# Buck.net
KiCad netlist of a schematic drawn in EAGLE
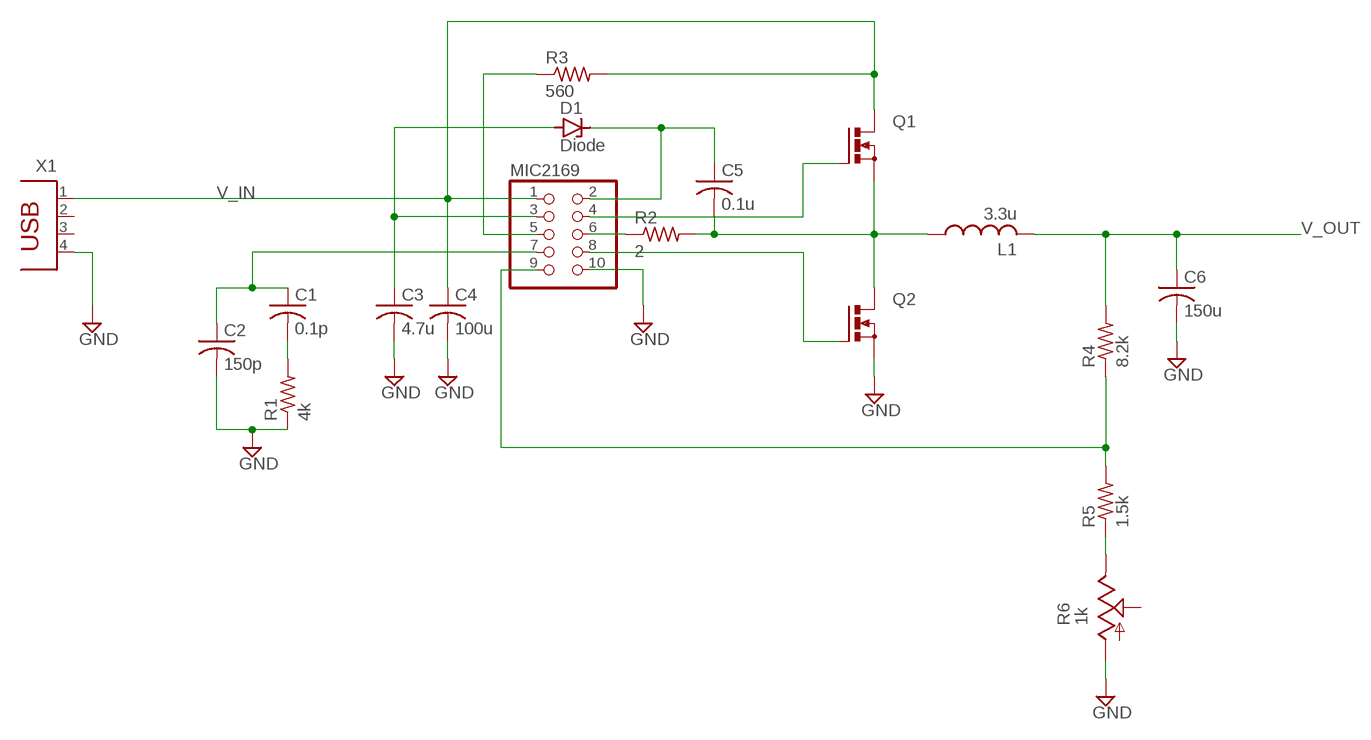
[diagram p0: schematic, sheet 1]

(export (version "E")
  (design (tool "Eeschema 10.0.6"))
  (components
    (comp (ref "C1")
      (value "0.1p")
      (footprint "eagle-import:C0805")
      (libsource (lib "eagle-import") (part "C-USC0805"))
    )
    (comp (ref "C2")
      (value "150p")
      (footprint "eagle-import:C0805")
      (libsource (lib "eagle-import") (part "C-USC0805"))
    )
    (comp (ref "C3")
      (value "4.7u")
      (footprint "eagle-import:C0805")
      (libsource (lib "eagle-import") (part "C-USC0805"))
    )
    (comp (ref "C4")
      (value "100u")
      (footprint "eagle-import:C0805")
      (libsource (lib "eagle-import") (part "C-USC0805"))
    )
    (comp (ref "C5")
      (value "0.1u")
      (footprint "eagle-import:C0805")
      (libsource (lib "eagle-import") (part "C-USC0805"))
    )
    (comp (ref "C6")
      (value "150u")
      (footprint "eagle-import:C0805")
      (libsource (lib "eagle-import") (part "C-USC0805"))
    )
    (comp (ref "D1")
      (value "Diode")
      (footprint "eagle-import:DO35Z10")
      (libsource (lib "eagle-import") (part "1N821"))
    )
    (comp (ref "L1")
      (value "3.3u")
      (footprint "eagle-import:L2825P")
      (libsource (lib "eagle-import") (part "L-USL2825P"))
    )
    (comp (ref "MIC2169")
      (value "PINHD-2X5")
      (footprint "eagle-import:2X05")
      (libsource (lib "eagle-import") (part "PINHD-2X5"))
    )
    (comp (ref "R1")
      (value "4k")
      (footprint "eagle-import:R0805")
      (libsource (lib "eagle-import") (part "R-US_R0805"))
    )
    (comp (ref "R2")
      (value "2")
      (footprint "eagle-import:R0805")
      (libsource (lib "eagle-import") (part "R-US_R0805"))
    )
    (comp (ref "R3")
      (value "560")
      (footprint "eagle-import:R0805")
      (libsource (lib "eagle-import") (part "R-US_R0805"))
    )
    (comp (ref "R4")
      (value "8.2k")
      (footprint "eagle-import:R0805")
      (libsource (lib "eagle-import") (part "R-US_R0805"))
    )
    (comp (ref "R5")
      (value "1.5k")
      (footprint "eagle-import:R0805")
      (libsource (lib "eagle-import") (part "R-US_R0805"))
    )
    (comp (ref "R6")
      (value "1k")
      (footprint "eagle-import:3223G")
      (libsource (lib "eagle-import") (part "TRIM_US-3223G"))
    )
    (comp (ref "X1")
      (value "PN61729")
      (footprint "eagle-import:PN61729")
      (libsource (lib "eagle-import") (part "PN61729"))
    )
  )
  (nets
    (net (code "1") (name "/V_IN") (class "Default")
      (node (ref "C4") (pin "1") (pinfunction "1_1") (pintype "passive"))
      (node (ref "MIC2169") (pin "1") (pinfunction "1_1") (pintype "passive"))
      (node (ref "R3") (pin "2") (pinfunction "2_2") (pintype "passive"))
      (node (ref "X1") (pin "1") (pinfunction "1_1") (pintype "passive"))
    )
    (net (code "2") (name "/V_OUT") (class "Default")
      (node (ref "C6") (pin "1") (pinfunction "1_1") (pintype "passive"))
      (node (ref "L1") (pin "2") (pinfunction "2_2") (pintype "passive"))
      (node (ref "R4") (pin "2") (pinfunction "2_2") (pintype "passive"))
    )
    (net (code "3") (name "GND") (class "Default")
      (node (ref "C2") (pin "2") (pinfunction "2_2") (pintype "passive"))
      (node (ref "C3") (pin "2") (pinfunction "2_2") (pintype "passive"))
      (node (ref "C4") (pin "2") (pinfunction "2_2") (pintype "passive"))
      (node (ref "C6") (pin "2") (pinfunction "2_2") (pintype "passive"))
      (node (ref "MIC2169") (pin "10") (pinfunction "10_10") (pintype "passive"))
      (node (ref "R1") (pin "1") (pinfunction "1_1") (pintype "passive"))
      (node (ref "R6") (pin "1") (pinfunction "A_1") (pintype "passive"))
      (node (ref "X1") (pin "4") (pinfunction "4_4") (pintype "passive"))
    )
    (net (code "4") (name "Net-(C1-Pad1)") (class "Default")
      (node (ref "C1") (pin "1") (pinfunction "1_1") (pintype "passive"))
      (node (ref "C2") (pin "1") (pinfunction "1_1") (pintype "passive"))
      (node (ref "MIC2169") (pin "7") (pinfunction "7_7") (pintype "passive"))
    )
    (net (code "5") (name "Net-(C1-Pad2)") (class "Default")
      (node (ref "C1") (pin "2") (pinfunction "2_2") (pintype "passive"))
      (node (ref "R1") (pin "2") (pinfunction "2_2") (pintype "passive"))
    )
    (net (code "6") (name "Net-(C3-Pad1)") (class "Default")
      (node (ref "C3") (pin "1") (pinfunction "1_1") (pintype "passive"))
      (node (ref "D1") (pin "A") (pinfunction "A_A") (pintype "passive"))
      (node (ref "MIC2169") (pin "3") (pinfunction "3_3") (pintype "passive"))
    )
    (net (code "7") (name "Net-(C5-Pad1)") (class "Default")
      (node (ref "C5") (pin "1") (pinfunction "1_1") (pintype "passive"))
      (node (ref "D1") (pin "C") (pinfunction "C_C") (pintype "passive"))
      (node (ref "MIC2169") (pin "2") (pinfunction "2_2") (pintype "passive"))
    )
    (net (code "8") (name "Net-(C5-Pad2)") (class "Default")
      (node (ref "C5") (pin "2") (pinfunction "2_2") (pintype "passive"))
      (node (ref "L1") (pin "1") (pinfunction "1_1") (pintype "passive"))
      (node (ref "R2") (pin "2") (pinfunction "2_2") (pintype "passive"))
    )
    (net (code "9") (name "Net-(MIC2169-Pad5)") (class "Default")
      (node (ref "MIC2169") (pin "5") (pinfunction "5_5") (pintype "passive"))
      (node (ref "R3") (pin "1") (pinfunction "1_1") (pintype "passive"))
    )
    (net (code "10") (name "Net-(MIC2169-Pad6)") (class "Default")
      (node (ref "MIC2169") (pin "6") (pinfunction "6_6") (pintype "passive"))
      (node (ref "R2") (pin "1") (pinfunction "1_1") (pintype "passive"))
    )
    (net (code "11") (name "Net-(MIC2169-Pad9)") (class "Default")
      (node (ref "MIC2169") (pin "9") (pinfunction "9_9") (pintype "passive"))
      (node (ref "R4") (pin "1") (pinfunction "1_1") (pintype "passive"))
      (node (ref "R5") (pin "2") (pinfunction "2_2") (pintype "passive"))
    )
    (net (code "12") (name "Net-(R6-E)") (class "Default")
      (node (ref "R5") (pin "1") (pinfunction "1_1") (pintype "passive"))
      (node (ref "R6") (pin "3") (pinfunction "E_3") (pintype "passive"))
    )
    (net (code "13") (name "unconnected-(MIC2169-Pad4)") (class "Default")
      (node (ref "MIC2169") (pin "4") (pinfunction "4_4") (pintype "passive"))
    )
    (net (code "14") (name "unconnected-(MIC2169-Pad8)") (class "Default")
      (node (ref "MIC2169") (pin "8") (pinfunction "8_8") (pintype "passive"))
    )
    (net (code "15") (name "unconnected-(R6-S-Pad2)") (class "Default")
      (node (ref "R6") (pin "2") (pinfunction "S_2") (pintype "passive"))
    )
    (net (code "16") (name "unconnected-(X1-Pad2)") (class "Default")
      (node (ref "X1") (pin "2") (pinfunction "2_2") (pintype "passive"))
    )
    (net (code "17") (name "unconnected-(X1-Pad3)") (class "Default")
      (node (ref "X1") (pin "3") (pinfunction "3_3") (pintype "passive"))
    )
  )
)
